# M453A.net
KiCad netlist of a schematic drawn in EAGLE
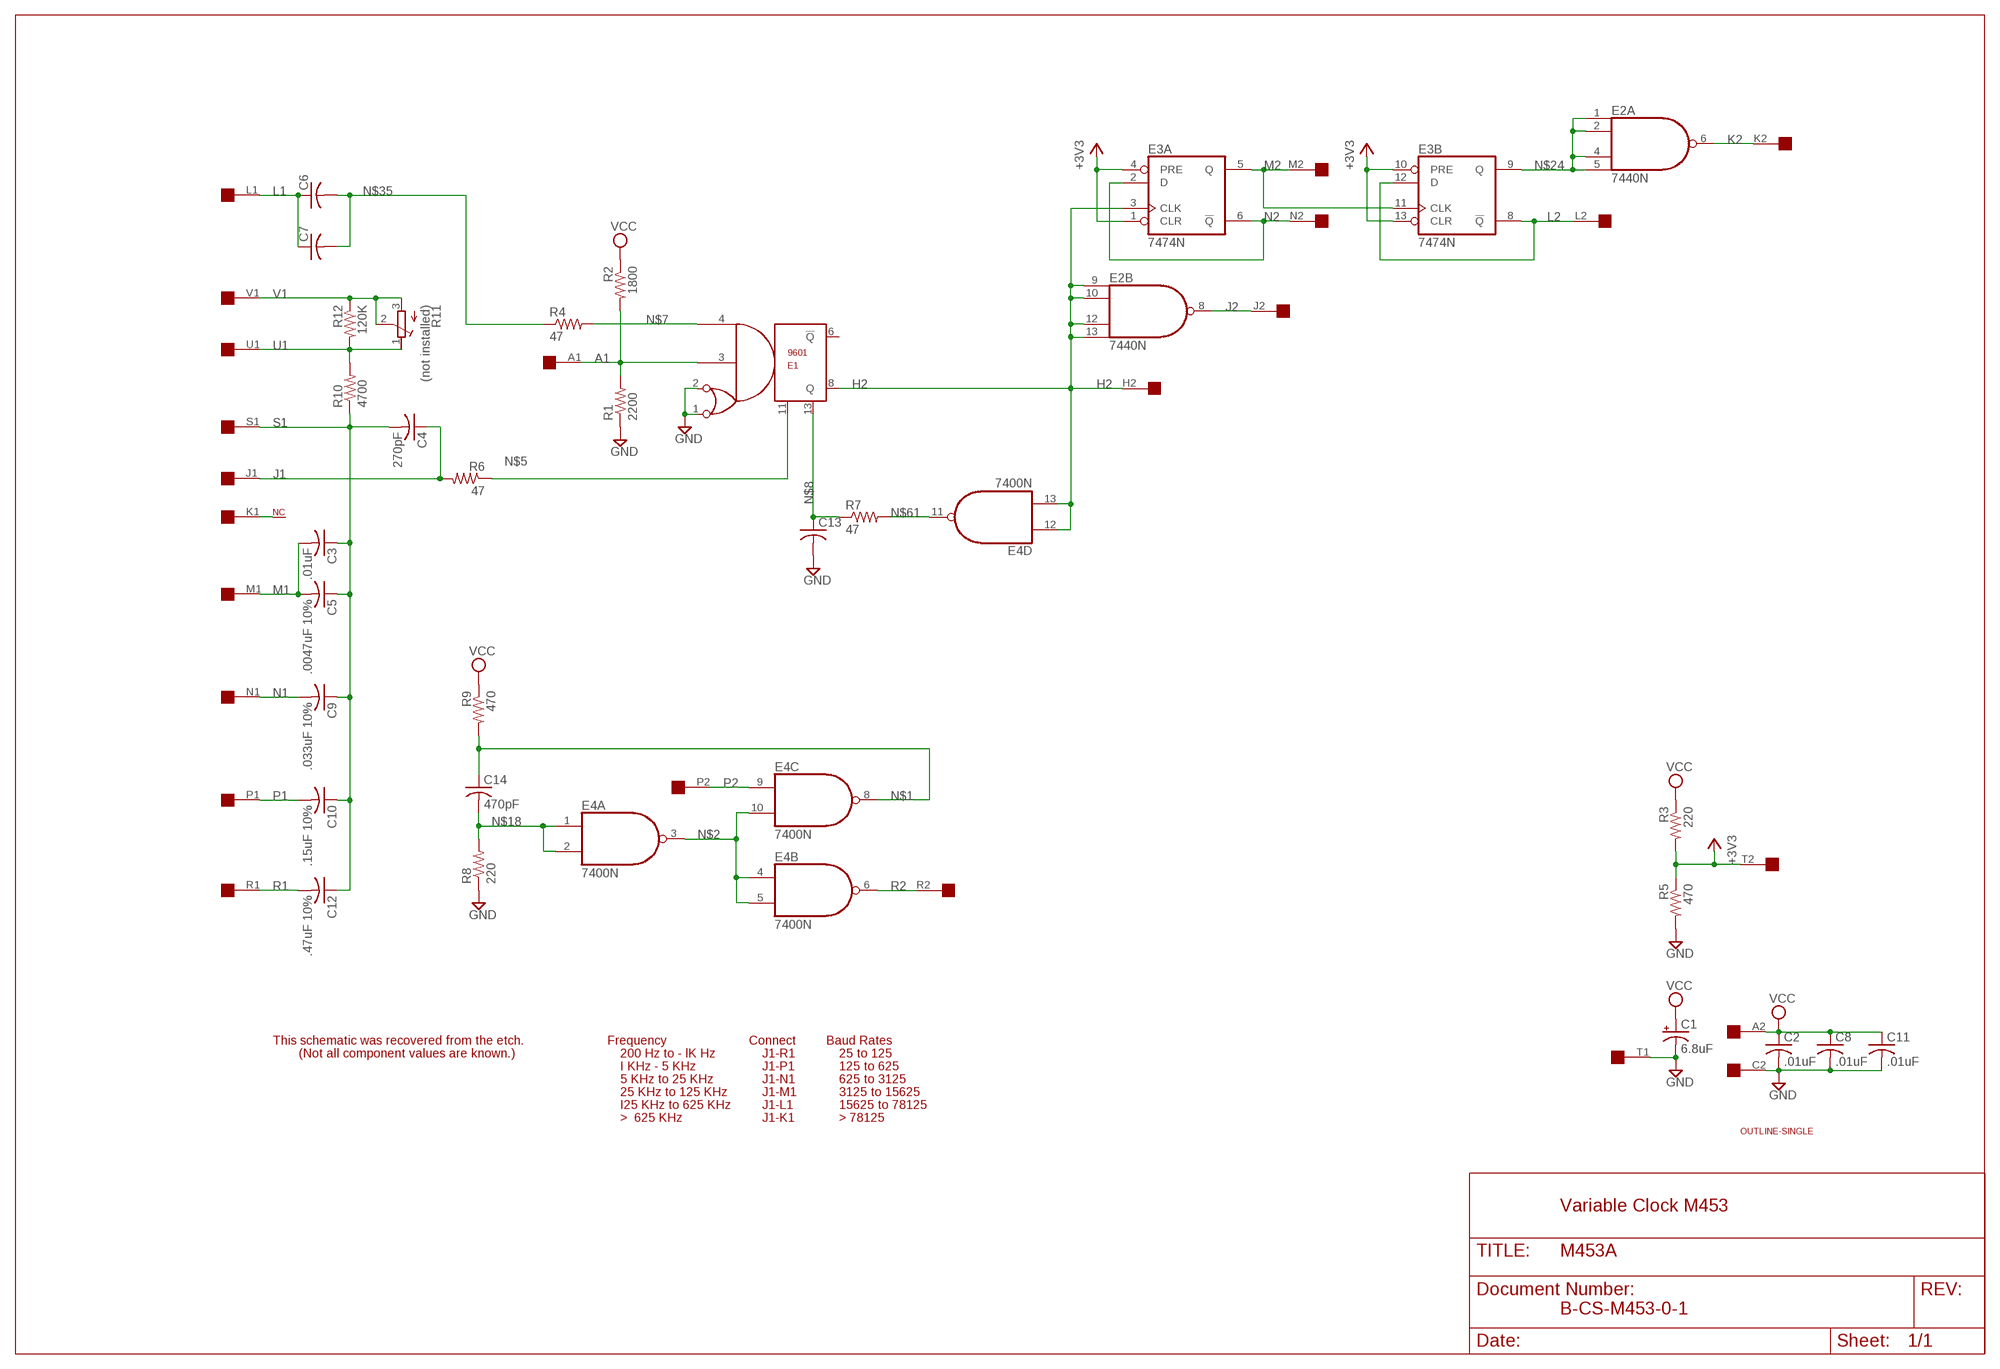
[diagram p0: schematic, sheet 1]

(export (version "E")
  (design (tool "Eeschema 10.0.6"))
  (components
    (comp (ref "C1")
      (value "6.8uF")
      (footprint "eagle-import:E12-8")
      (libsource (lib "eagle-import") (part "CPOL-USE20-8AXIAL"))
    )
    (comp (ref "C2")
      (value ".01uF")
      (footprint "eagle-import:C050-025X075")
      (libsource (lib "eagle-import") (part "C-US050-025X075"))
    )
    (comp (ref "C3")
      (value ".01uF")
      (footprint "eagle-import:C050-025X075")
      (libsource (lib "eagle-import") (part "C-US050-025X075"))
    )
    (comp (ref "C4")
      (value "270pF")
      (footprint "eagle-import:C050-025X075")
      (libsource (lib "eagle-import") (part "C-US050-025X075"))
    )
    (comp (ref "C5")
      (value ".0047uF 10%")
      (footprint "eagle-import:C225-062X268")
      (libsource (lib "eagle-import") (part "C-US225-062X268"))
    )
    (comp (ref "C6")
      (value "C-US050-025X075")
      (footprint "eagle-import:C050-025X075")
      (libsource (lib "eagle-import") (part "C-US050-025X075"))
    )
    (comp (ref "C7")
      (value "C-US050-025X075")
      (footprint "eagle-import:C050-025X075")
      (libsource (lib "eagle-import") (part "C-US050-025X075"))
    )
    (comp (ref "C8")
      (value ".01uF")
      (footprint "eagle-import:C050-025X075")
      (libsource (lib "eagle-import") (part "C-US050-025X075"))
    )
    (comp (ref "C9")
      (value ".033uF 10%")
      (footprint "eagle-import:C225-062X268")
      (libsource (lib "eagle-import") (part "C-US225-062X268"))
    )
    (comp (ref "C10")
      (value ".15uF 10%")
      (footprint "eagle-import:C325-137X374")
      (libsource (lib "eagle-import") (part "C-US325-137X374"))
    )
    (comp (ref "C11")
      (value ".01uF")
      (footprint "eagle-import:C050-025X075")
      (libsource (lib "eagle-import") (part "C-US050-025X075"))
    )
    (comp (ref "C12")
      (value ".47uF 10%")
      (footprint "eagle-import:C375-155X418")
      (libsource (lib "eagle-import") (part "C-US375-155X418"))
    )
    (comp (ref "C13")
      (value "C-US050-025X075")
      (footprint "eagle-import:C050-025X075")
      (libsource (lib "eagle-import") (part "C-US050-025X075"))
    )
    (comp (ref "C14")
      (value "470pF")
      (footprint "eagle-import:C050-025X075")
      (libsource (lib "eagle-import") (part "C-US050-025X075"))
    )
    (comp (ref "E1")
      (value "9601")
      (footprint "eagle-import:DIL14")
      (libsource (lib "eagle-import") (part "9601"))
    )
    (comp (ref "E2")
      (value "7440N")
      (footprint "eagle-import:DIL14")
      (libsource (lib "eagle-import") (part "7420NS"))
    )
    (comp (ref "E3")
      (value "7474N")
      (footprint "eagle-import:DIL14")
      (libsource (lib "eagle-import") (part "7474NS"))
    )
    (comp (ref "E4")
      (value "7400N")
      (footprint "eagle-import:DIL14")
      (libsource (lib "eagle-import") (part "7400N"))
    )
    (comp (ref "R1")
      (value "2200")
      (footprint "eagle-import:0207_10")
      (libsource (lib "eagle-import") (part "R-US_0207/10"))
    )
    (comp (ref "R2")
      (value "1800")
      (footprint "eagle-import:0207_10")
      (libsource (lib "eagle-import") (part "R-US_0207/10"))
    )
    (comp (ref "R3")
      (value "220")
      (footprint "eagle-import:0207_10")
      (libsource (lib "eagle-import") (part "R-US_0207/10"))
    )
    (comp (ref "R4")
      (value "47")
      (footprint "eagle-import:0207_10")
      (libsource (lib "eagle-import") (part "R-US_0207/10"))
    )
    (comp (ref "R5")
      (value "470")
      (footprint "eagle-import:0207_10")
      (libsource (lib "eagle-import") (part "R-US_0207/10"))
    )
    (comp (ref "R6")
      (value "47")
      (footprint "eagle-import:0207_10")
      (libsource (lib "eagle-import") (part "R-US_0207/10"))
    )
    (comp (ref "R7")
      (value "47")
      (footprint "eagle-import:0207_10")
      (libsource (lib "eagle-import") (part "R-US_0207/10"))
    )
    (comp (ref "R8")
      (value "220")
      (footprint "eagle-import:0207_10")
      (libsource (lib "eagle-import") (part "R-US_0207/10"))
    )
    (comp (ref "R9")
      (value "470")
      (footprint "eagle-import:0207_10")
      (libsource (lib "eagle-import") (part "R-US_0207/10"))
    )
    (comp (ref "R10")
      (value "4700")
      (footprint "eagle-import:0207_10")
      (libsource (lib "eagle-import") (part "R-US_0207/10"))
    )
    (comp (ref "R11")
      (value "(not installed)")
      (footprint "eagle-import:3006Y")
      (libsource (lib "eagle-import") (part "275P"))
    )
    (comp (ref "R12")
      (value "120K")
      (footprint "eagle-import:0207_10")
      (libsource (lib "eagle-import") (part "R-US_0207/10"))
    )
    (comp (ref "U$1")
      (value "OUTLINE-SINGLE")
      (footprint "eagle-import:SINGLE")
      (libsource (lib "eagle-import") (part "OUTLINE-SINGLE"))
    )
    (comp (ref "U$3")
      (value "SINGLE")
      (footprint "eagle-import:EDGE-CON2")
      (libsource (lib "eagle-import") (part "SINGLE"))
    )
  )
  (nets
    (net (code "1") (name "+3V3") (class "Default")
      (node (ref "E3") (pin "1") (pinfunction "CLR_1") (pintype "input"))
      (node (ref "E3") (pin "10") (pinfunction "PRE_10") (pintype "input"))
      (node (ref "E3") (pin "13") (pinfunction "CLR_13") (pintype "input"))
      (node (ref "E3") (pin "4") (pinfunction "PRE_4") (pintype "input"))
      (node (ref "R3") (pin "2") (pinfunction "2_2") (pintype "passive"))
      (node (ref "R5") (pin "1") (pinfunction "1_1") (pintype "passive"))
      (node (ref "U$3") (pin "T2") (pinfunction "1_T2") (pintype "bidirectional"))
    )
    (net (code "2") (name "/A1") (class "Default")
      (node (ref "E1") (pin "3") (pinfunction "P$3_3") (pintype "input"))
      (node (ref "R1") (pin "2") (pinfunction "2_2") (pintype "passive"))
      (node (ref "R2") (pin "2") (pinfunction "2_2") (pintype "passive"))
      (node (ref "U$3") (pin "A1") (pinfunction "1_A1") (pintype "bidirectional"))
    )
    (net (code "3") (name "/H2") (class "Default")
      (node (ref "E1") (pin "8") (pinfunction "Q_8") (pintype "output"))
      (node (ref "E2") (pin "10") (pinfunction "I1_10") (pintype "input"))
      (node (ref "E2") (pin "12") (pinfunction "I2_12") (pintype "input"))
      (node (ref "E2") (pin "13") (pinfunction "I3_13") (pintype "input"))
      (node (ref "E2") (pin "9") (pinfunction "I0_9") (pintype "input"))
      (node (ref "E3") (pin "3") (pinfunction "CLK_3") (pintype "input"))
      (node (ref "E4") (pin "12") (pinfunction "I0_12") (pintype "input"))
      (node (ref "E4") (pin "13") (pinfunction "I1_13") (pintype "input"))
      (node (ref "U$3") (pin "H2") (pinfunction "1_H2") (pintype "bidirectional"))
    )
    (net (code "4") (name "/J1") (class "Default")
      (node (ref "C4") (pin "1") (pinfunction "1_1") (pintype "passive"))
      (node (ref "R6") (pin "2") (pinfunction "2_2") (pintype "passive"))
      (node (ref "U$3") (pin "J1") (pinfunction "1_J1") (pintype "bidirectional"))
    )
    (net (code "5") (name "/J2") (class "Default")
      (node (ref "E2") (pin "8") (pinfunction "O_8") (pintype "output"))
      (node (ref "U$3") (pin "J2") (pinfunction "1_J2") (pintype "bidirectional"))
    )
    (net (code "6") (name "/K2") (class "Default")
      (node (ref "E2") (pin "6") (pinfunction "O_6") (pintype "output"))
      (node (ref "U$3") (pin "K2") (pinfunction "1_K2") (pintype "bidirectional"))
    )
    (net (code "7") (name "/L1") (class "Default")
      (node (ref "C6") (pin "1") (pinfunction "1_1") (pintype "passive"))
      (node (ref "C7") (pin "1") (pinfunction "1_1") (pintype "passive"))
      (node (ref "U$3") (pin "L1") (pinfunction "1_L1") (pintype "bidirectional"))
    )
    (net (code "8") (name "/L2") (class "Default")
      (node (ref "E3") (pin "12") (pinfunction "D_12") (pintype "input"))
      (node (ref "E3") (pin "8") (pinfunction "~{Q}_8") (pintype "output"))
      (node (ref "U$3") (pin "L2") (pinfunction "1_L2") (pintype "bidirectional"))
    )
    (net (code "9") (name "/M1") (class "Default")
      (node (ref "C3") (pin "2") (pinfunction "2_2") (pintype "passive"))
      (node (ref "C5") (pin "2") (pinfunction "2_2") (pintype "passive"))
      (node (ref "U$3") (pin "M1") (pinfunction "1_M1") (pintype "bidirectional"))
    )
    (net (code "10") (name "/M2") (class "Default")
      (node (ref "E3") (pin "11") (pinfunction "CLK_11") (pintype "input"))
      (node (ref "E3") (pin "5") (pinfunction "Q_5") (pintype "output"))
      (node (ref "U$3") (pin "M2") (pinfunction "1_M2") (pintype "bidirectional"))
    )
    (net (code "11") (name "/N$1") (class "Default")
      (node (ref "C14") (pin "1") (pinfunction "1_1") (pintype "passive"))
      (node (ref "E4") (pin "8") (pinfunction "O_8") (pintype "output"))
      (node (ref "R9") (pin "2") (pinfunction "2_2") (pintype "passive"))
    )
    (net (code "12") (name "/N$2") (class "Default")
      (node (ref "E4") (pin "10") (pinfunction "I1_10") (pintype "input"))
      (node (ref "E4") (pin "3") (pinfunction "O_3") (pintype "output"))
      (node (ref "E4") (pin "4") (pinfunction "I0_4") (pintype "input"))
      (node (ref "E4") (pin "5") (pinfunction "I1_5") (pintype "input"))
    )
    (net (code "13") (name "/N$5") (class "Default")
      (node (ref "E1") (pin "11") (pinfunction "P$5_11") (pintype "bidirectional"))
      (node (ref "R6") (pin "1") (pinfunction "1_1") (pintype "passive"))
    )
    (net (code "14") (name "/N$7") (class "Default")
      (node (ref "E1") (pin "4") (pinfunction "P$4_4") (pintype "input"))
      (node (ref "R4") (pin "2") (pinfunction "2_2") (pintype "passive"))
    )
    (net (code "15") (name "/N$8") (class "Default")
      (node (ref "C13") (pin "1") (pinfunction "1_1") (pintype "passive"))
      (node (ref "E1") (pin "13") (pinfunction "P$6_13") (pintype "bidirectional"))
      (node (ref "R7") (pin "1") (pinfunction "1_1") (pintype "passive"))
    )
    (net (code "16") (name "/N$18") (class "Default")
      (node (ref "C14") (pin "2") (pinfunction "2_2") (pintype "passive"))
      (node (ref "E4") (pin "1") (pinfunction "I0_1") (pintype "input"))
      (node (ref "E4") (pin "2") (pinfunction "I1_2") (pintype "input"))
      (node (ref "R8") (pin "2") (pinfunction "2_2") (pintype "passive"))
    )
    (net (code "17") (name "/N$24") (class "Default")
      (node (ref "E2") (pin "1") (pinfunction "I0_1") (pintype "input"))
      (node (ref "E2") (pin "2") (pinfunction "I1_2") (pintype "input"))
      (node (ref "E2") (pin "4") (pinfunction "I2_4") (pintype "input"))
      (node (ref "E2") (pin "5") (pinfunction "I3_5") (pintype "input"))
      (node (ref "E3") (pin "9") (pinfunction "Q_9") (pintype "output"))
    )
    (net (code "18") (name "/N$35") (class "Default")
      (node (ref "C6") (pin "2") (pinfunction "2_2") (pintype "passive"))
      (node (ref "C7") (pin "2") (pinfunction "2_2") (pintype "passive"))
      (node (ref "R4") (pin "1") (pinfunction "1_1") (pintype "passive"))
    )
    (net (code "19") (name "/N$61") (class "Default")
      (node (ref "E4") (pin "11") (pinfunction "O_11") (pintype "output"))
      (node (ref "R7") (pin "2") (pinfunction "2_2") (pintype "passive"))
    )
    (net (code "20") (name "/N1") (class "Default")
      (node (ref "C9") (pin "2") (pinfunction "2_2") (pintype "passive"))
      (node (ref "U$3") (pin "N1") (pinfunction "1_N1") (pintype "bidirectional"))
    )
    (net (code "21") (name "/N2") (class "Default")
      (node (ref "E3") (pin "2") (pinfunction "D_2") (pintype "input"))
      (node (ref "E3") (pin "6") (pinfunction "~{Q}_6") (pintype "output"))
      (node (ref "U$3") (pin "N2") (pinfunction "1_N2") (pintype "bidirectional"))
    )
    (net (code "22") (name "/P1") (class "Default")
      (node (ref "C10") (pin "2") (pinfunction "2_2") (pintype "passive"))
      (node (ref "U$3") (pin "P1") (pinfunction "1_P1") (pintype "bidirectional"))
    )
    (net (code "23") (name "/P2") (class "Default")
      (node (ref "E4") (pin "9") (pinfunction "I0_9") (pintype "input"))
      (node (ref "U$3") (pin "P2") (pinfunction "1_P2") (pintype "bidirectional"))
    )
    (net (code "24") (name "/R1") (class "Default")
      (node (ref "C12") (pin "2") (pinfunction "2_2") (pintype "passive"))
      (node (ref "U$3") (pin "R1") (pinfunction "1_R1") (pintype "bidirectional"))
    )
    (net (code "25") (name "/R2") (class "Default")
      (node (ref "E4") (pin "6") (pinfunction "O_6") (pintype "output"))
      (node (ref "U$3") (pin "R2") (pinfunction "1_R2") (pintype "bidirectional"))
    )
    (net (code "26") (name "/S1") (class "Default")
      (node (ref "C10") (pin "1") (pinfunction "1_1") (pintype "passive"))
      (node (ref "C12") (pin "1") (pinfunction "1_1") (pintype "passive"))
      (node (ref "C3") (pin "1") (pinfunction "1_1") (pintype "passive"))
      (node (ref "C4") (pin "2") (pinfunction "2_2") (pintype "passive"))
      (node (ref "C5") (pin "1") (pinfunction "1_1") (pintype "passive"))
      (node (ref "C9") (pin "1") (pinfunction "1_1") (pintype "passive"))
      (node (ref "R10") (pin "1") (pinfunction "1_1") (pintype "passive"))
      (node (ref "U$3") (pin "S1") (pinfunction "1_S1") (pintype "bidirectional"))
    )
    (net (code "27") (name "/U1") (class "Default")
      (node (ref "R10") (pin "2") (pinfunction "2_2") (pintype "passive"))
      (node (ref "R11") (pin "1") (pinfunction "A_1") (pintype "passive"))
      (node (ref "R12") (pin "2") (pinfunction "2_2") (pintype "passive"))
      (node (ref "U$3") (pin "U1") (pinfunction "1_U1") (pintype "bidirectional"))
    )
    (net (code "28") (name "/V1") (class "Default")
      (node (ref "R11") (pin "2") (pinfunction "S_2") (pintype "passive"))
      (node (ref "R11") (pin "3") (pinfunction "E_3") (pintype "passive"))
      (node (ref "R12") (pin "1") (pinfunction "1_1") (pintype "passive"))
      (node (ref "U$3") (pin "V1") (pinfunction "1_V1") (pintype "bidirectional"))
    )
    (net (code "29") (name "GND") (class "Default")
      (node (ref "C1") (pin "-") (pinfunction "-_-") (pintype "passive"))
      (node (ref "C11") (pin "2") (pinfunction "2_2") (pintype "passive"))
      (node (ref "C13") (pin "2") (pinfunction "2_2") (pintype "passive"))
      (node (ref "C2") (pin "2") (pinfunction "2_2") (pintype "passive"))
      (node (ref "C8") (pin "2") (pinfunction "2_2") (pintype "passive"))
      (node (ref "E1") (pin "1") (pinfunction "P$1_1") (pintype "input"))
      (node (ref "E1") (pin "2") (pinfunction "P$2_2") (pintype "input"))
      (node (ref "R1") (pin "1") (pinfunction "1_1") (pintype "passive"))
      (node (ref "R5") (pin "2") (pinfunction "2_2") (pintype "passive"))
      (node (ref "R8") (pin "1") (pinfunction "1_1") (pintype "passive"))
      (node (ref "U$3") (pin "C2") (pinfunction "1_C2") (pintype "bidirectional"))
      (node (ref "U$3") (pin "T1") (pinfunction "1_T1") (pintype "bidirectional"))
    )
    (net (code "30") (name "NC") (class "Default")
      (node (ref "U$3") (pin "K1") (pinfunction "1_K1") (pintype "bidirectional"))
    )
    (net (code "31") (name "VCC") (class "Default")
      (node (ref "C1") (pin "+") (pinfunction "+_+") (pintype "passive"))
      (node (ref "C11") (pin "1") (pinfunction "1_1") (pintype "passive"))
      (node (ref "C2") (pin "1") (pinfunction "1_1") (pintype "passive"))
      (node (ref "C8") (pin "1") (pinfunction "1_1") (pintype "passive"))
      (node (ref "R2") (pin "1") (pinfunction "1_1") (pintype "passive"))
      (node (ref "R3") (pin "1") (pinfunction "1_1") (pintype "passive"))
      (node (ref "R9") (pin "1") (pinfunction "1_1") (pintype "passive"))
      (node (ref "U$3") (pin "A2") (pinfunction "1_A2") (pintype "bidirectional"))
    )
    (net (code "32") (name "unconnected-(E1A-~{Q}-Pad6)") (class "Default")
      (node (ref "E1") (pin "6") (pinfunction "~{Q}_6") (pintype "output"))
    )
  )
)
